# Arduino_Leonardo-REV3b_-.net
KiCad netlist of a schematic drawn in EAGLE
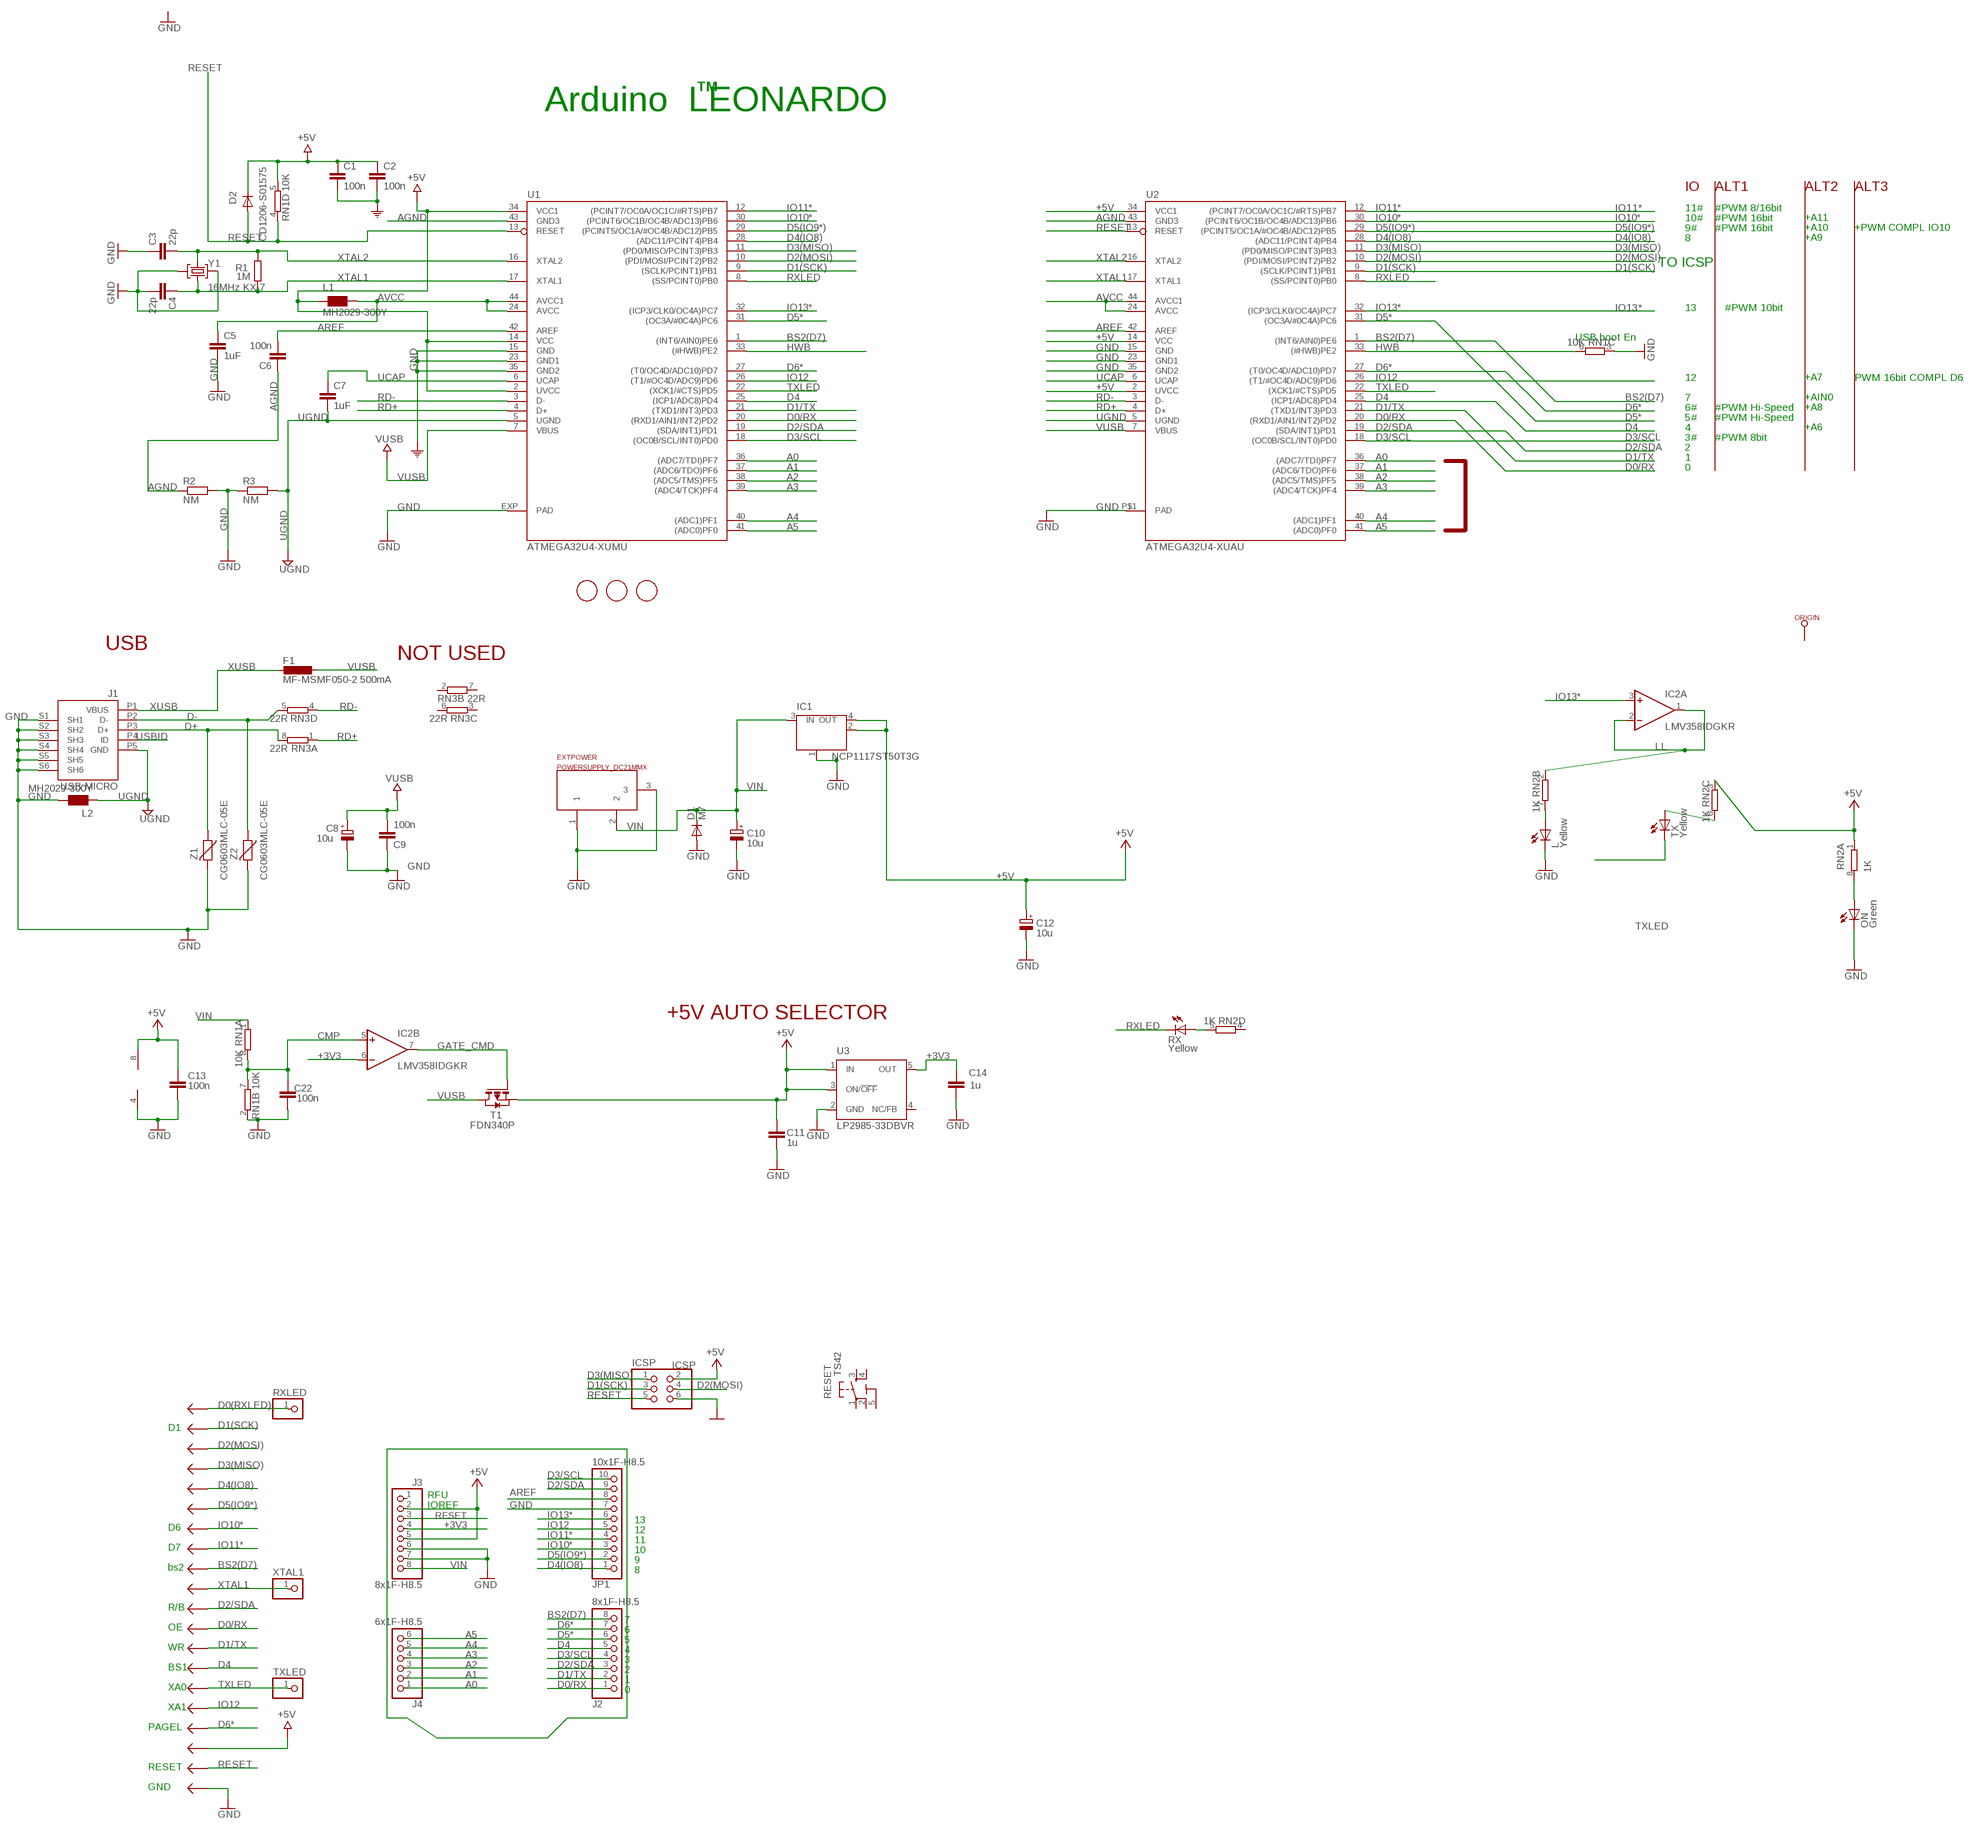
[diagram p0: schematic, sheet 1]

(export (version "E")
  (design (tool "Eeschema 10.0.6"))
  (components
    (comp (ref "C1")
      (value "100n")
      (footprint "eagle-import:C0603-ROUND")
      (libsource (lib "eagle-import") (part "C-EUC0603"))
    )
    (comp (ref "C2")
      (value "100n")
      (footprint "eagle-import:C0603-ROUND")
      (libsource (lib "eagle-import") (part "C-EUC0603"))
    )
    (comp (ref "C3")
      (value "22p")
      (footprint "eagle-import:C0603-ROUND")
      (libsource (lib "eagle-import") (part "C-EUC0603"))
    )
    (comp (ref "C4")
      (value "22p")
      (footprint "eagle-import:C0603-ROUND")
      (libsource (lib "eagle-import") (part "C-EUC0603"))
    )
    (comp (ref "C5")
      (value "1uF")
      (footprint "eagle-import:C0603-ROUND")
      (libsource (lib "eagle-import") (part "C-EUC0603"))
    )
    (comp (ref "C6")
      (value "100n")
      (footprint "eagle-import:C0603-ROUND")
      (libsource (lib "eagle-import") (part "C-EUC0603"))
    )
    (comp (ref "C7")
      (value "1uF")
      (footprint "eagle-import:C0603-ROUND")
      (libsource (lib "eagle-import") (part "C-EUC0603"))
    )
    (comp (ref "C8")
      (value "10u")
      (footprint "eagle-import:SMC_B")
      (libsource (lib "eagle-import") (part "CPOL-EUSMCB"))
    )
    (comp (ref "C9")
      (value "100n")
      (footprint "eagle-import:C0603-ROUND")
      (libsource (lib "eagle-import") (part "C-EUC0603"))
    )
    (comp (ref "C10")
      (value "10u")
      (footprint "eagle-import:SMC_B")
      (libsource (lib "eagle-import") (part "CPOL-EUSMCB"))
    )
    (comp (ref "C11")
      (value "1u")
      (footprint "eagle-import:C0603-ROUND")
      (libsource (lib "eagle-import") (part "C-EUC0603"))
    )
    (comp (ref "C12")
      (value "10u")
      (footprint "eagle-import:SMC_B")
      (libsource (lib "eagle-import") (part "CPOL-EUSMCB"))
    )
    (comp (ref "C13")
      (value "100n")
      (footprint "eagle-import:C0603-ROUND")
      (libsource (lib "eagle-import") (part "C-EUC0603"))
    )
    (comp (ref "C14")
      (value "1u")
      (footprint "eagle-import:C0603-ROUND")
      (libsource (lib "eagle-import") (part "C-EUC0603"))
    )
    (comp (ref "C22")
      (value "100n")
      (footprint "eagle-import:C0603-ROUND")
      (libsource (lib "eagle-import") (part "C-EUC0603"))
    )
    (comp (ref "D1")
      (value "M7")
      (footprint "eagle-import:SMB")
      (libsource (lib "eagle-import") (part "DIODE-SMB"))
    )
    (comp (ref "D2")
      (value "CD1206-S01575")
      (footprint "eagle-import:MINIMELF")
      (libsource (lib "eagle-import") (part "DIODE-MINIMELF"))
    )
    (comp (ref "EXTPOWER")
      (value "POWERSUPPLY_DC21MMX")
      (footprint "eagle-import:POWERSUPPLY_DC-21MM")
      (libsource (lib "eagle-import") (part "POWERSUPPLY_DC21MMX"))
    )
    (comp (ref "F1")
      (value "MF-MSMF050-2 500mA")
      (footprint "eagle-import:L1812")
      (libsource (lib "eagle-import") (part "L-EUL1812"))
    )
    (comp (ref "FID1")
      (value "FIDUCIALMOUNT")
      (footprint "eagle-import:FIDUCIA-MOUNT")
      (libsource (lib "eagle-import") (part "FIDUCIALMOUNT"))
    )
    (comp (ref "FID2")
      (value "FIDUCIALMOUNT")
      (footprint "eagle-import:FIDUCIA-MOUNT")
      (libsource (lib "eagle-import") (part "FIDUCIALMOUNT"))
    )
    (comp (ref "FID3")
      (value "FIDUCIALMOUNT")
      (footprint "eagle-import:FIDUCIA-MOUNT")
      (libsource (lib "eagle-import") (part "FIDUCIALMOUNT"))
    )
    (comp (ref "IC1")
      (value "NCP1117ST50T3G")
      (footprint "eagle-import:SOT223")
      (libsource (lib "eagle-import") (part "MC33269ST-3.3T3"))
    )
    (comp (ref "IC2")
      (value "LMV358IDGKR")
      (footprint "eagle-import:MSOP08")
      (libsource (lib "eagle-import") (part "LMV358?MMX"))
    )
    (comp (ref "ICSP")
      (value "ICSP")
      (footprint "eagle-import:2X03")
      (libsource (lib "eagle-import") (part "PINHD-2X3"))
    )
    (comp (ref "J1")
      (value "USB MICRO")
      (footprint "eagle-import:CON2_USB_MICRO_B_AT")
      (libsource (lib "eagle-import") (part "MYCON2_USB-MINI-B"))
    )
    (comp (ref "J2")
      (value "8x1F-H8.5")
      (footprint "eagle-import:1X08")
      (libsource (lib "eagle-import") (part "PINHD-1X8"))
    )
    (comp (ref "J3")
      (value "8x1F-H8.5")
      (footprint "eagle-import:1X08")
      (libsource (lib "eagle-import") (part "PINHD-1X8"))
    )
    (comp (ref "J4")
      (value "6x1F-H8.5")
      (footprint "eagle-import:1X06")
      (libsource (lib "eagle-import") (part "PINHD-1X6"))
    )
    (comp (ref "JP1")
      (value "10x1F-H8.5")
      (footprint "eagle-import:1X10")
      (libsource (lib "eagle-import") (part "PINHD-1X10"))
    )
    (comp (ref "L")
      (value "Yellow")
      (footprint "eagle-import:CHIPLED_0805")
      (libsource (lib "eagle-import") (part "LEDCHIPLED_0805"))
    )
    (comp (ref "L1")
      (value "MH2029-300Y")
      (footprint "eagle-import:0805")
      (libsource (lib "eagle-import") (part "WE-CBF_0805"))
    )
    (comp (ref "L2")
      (value "MH2029-300Y")
      (footprint "eagle-import:0805")
      (libsource (lib "eagle-import") (part "WE-CBF_0805"))
    )
    (comp (ref "ON")
      (value "Green")
      (footprint "eagle-import:CHIPLED_0805")
      (libsource (lib "eagle-import") (part "LEDCHIPLED_0805"))
    )
    (comp (ref "ORIGIN")
      (value "TP_SP")
      (footprint "eagle-import:TP-SP")
      (libsource (lib "eagle-import") (part "TP_SP"))
    )
    (comp (ref "R1")
      (value "1M")
      (footprint "eagle-import:R0603-ROUND")
      (libsource (lib "eagle-import") (part "R-EU_R0603"))
    )
    (comp (ref "R2")
      (value "NM")
      (footprint "eagle-import:R0402")
      (libsource (lib "eagle-import") (part "R-EU_R0402"))
    )
    (comp (ref "R3")
      (value "NM")
      (footprint "eagle-import:R0402")
      (libsource (lib "eagle-import") (part "R-EU_R0402"))
    )
    (comp (ref "RESET")
      (value "TS42")
      (footprint "eagle-import:TS42")
      (libsource (lib "eagle-import") (part "TS42"))
    )
    (comp (ref "RN1")
      (value "10K")
      (footprint "eagle-import:CAY16")
      (libsource (lib "eagle-import") (part "4R-NCAY16"))
    )
    (comp (ref "RN2")
      (value "1K")
      (footprint "eagle-import:CAY16")
      (libsource (lib "eagle-import") (part "4R-NCAY16"))
    )
    (comp (ref "RN3")
      (value "22R")
      (footprint "eagle-import:CAY16")
      (libsource (lib "eagle-import") (part "4R-NCAY16"))
    )
    (comp (ref "RX")
      (value "Yellow")
      (footprint "eagle-import:CHIPLED_0805")
      (libsource (lib "eagle-import") (part "LEDCHIPLED_0805"))
    )
    (comp (ref "RXLED")
      (value "PINHD-1X1")
      (footprint "eagle-import:1X01")
      (libsource (lib "eagle-import") (part "PINHD-1X1"))
    )
    (comp (ref "T1")
      (value "FDN340P")
      (footprint "eagle-import:SOT-23")
      (libsource (lib "eagle-import") (part "PMOSSOT23"))
    )
    (comp (ref "TX")
      (value "Yellow")
      (footprint "eagle-import:CHIPLED_0805")
      (libsource (lib "eagle-import") (part "LEDCHIPLED_0805"))
    )
    (comp (ref "TXLED")
      (value "PINHD-1X1")
      (footprint "eagle-import:1X01")
      (libsource (lib "eagle-import") (part "PINHD-1X1"))
    )
    (comp (ref "U$2")
      (value "PROGRAMMER_P_AVR")
      (footprint "eagle-import:PROGRAMMER_P_AVR")
      (libsource (lib "eagle-import") (part "PROGRAMMER_P_AVR"))
    )
    (comp (ref "U1")
      (value "ATMEGA32U4-XUMU")
      (footprint "eagle-import:QFN44ML7X7")
      (libsource (lib "eagle-import") (part "ATMEGA32U4-XUMU"))
    )
    (comp (ref "U2")
      (value "ATMEGA32U4-XUAU")
      (footprint "eagle-import:TQFP44-PAD")
      (libsource (lib "eagle-import") (part "ATMEGA32U4-XUAU"))
    )
    (comp (ref "U3")
      (value "LP2985-33DBVR")
      (footprint "eagle-import:SOT23-DBV")
      (libsource (lib "eagle-import") (part "LP2985-XXDBVR33"))
    )
    (comp (ref "XTAL1")
      (value "PINHD-1X1")
      (footprint "eagle-import:1X01")
      (libsource (lib "eagle-import") (part "PINHD-1X1"))
    )
    (comp (ref "Y1")
      (value "16MHz KX-7")
      (footprint "eagle-import:CRYSTAL-3.2-2.5")
      (libsource (lib "eagle-import") (part "CRYSTAL-3.2-2.5"))
    )
    (comp (ref "Z1")
      (value "CG0603MLC-05E")
      (footprint "eagle-import:CT_CN0603")
      (libsource (lib "eagle-import") (part "VARISTORCN0603"))
    )
    (comp (ref "Z2")
      (value "CG0603MLC-05E")
      (footprint "eagle-import:CT_CN0603")
      (libsource (lib "eagle-import") (part "VARISTORCN0603"))
    )
  )
  (nets
    (net (code "1") (name "+5V") (class "Default")
      (node (ref "C1") (pin "1") (pinfunction "1_1") (pintype "passive"))
      (node (ref "C11") (pin "2") (pinfunction "2_2") (pintype "passive"))
      (node (ref "C12") (pin "+") (pinfunction "+_+") (pintype "passive"))
      (node (ref "C13") (pin "1") (pinfunction "1_1") (pintype "passive"))
      (node (ref "C2") (pin "1") (pinfunction "1_1") (pintype "passive"))
      (node (ref "D2") (pin "C") (pinfunction "C_C") (pintype "passive"))
      (node (ref "IC1") (pin "2") (pinfunction "OUT_2") (pintype "passive"))
      (node (ref "IC1") (pin "4") (pinfunction "OUT_4") (pintype "passive"))
      (node (ref "IC2") (pin "8") (pinfunction "V+_8") (pintype "power_in"))
      (node (ref "ICSP") (pin "2") (pinfunction "2_2") (pintype "passive"))
      (node (ref "J3") (pin "2") (pinfunction "2_2") (pintype "passive"))
      (node (ref "J3") (pin "5") (pinfunction "5_5") (pintype "passive"))
      (node (ref "L1") (pin "1") (pinfunction "1_1") (pintype "passive"))
      (node (ref "RN1") (pin "5") (pinfunction "2_5") (pintype "passive"))
      (node (ref "RN2") (pin "1") (pinfunction "1_1") (pintype "passive"))
      (node (ref "RN2") (pin "3") (pinfunction "1_3") (pintype "passive"))
      (node (ref "T1") (pin "2") (pinfunction "S_2") (pintype "passive"))
      (node (ref "U$2") (pin "VCC") (pinfunction "VCC_VCC") (pintype "bidirectional"))
      (node (ref "U1") (pin "14") (pinfunction "VCC_14") (pintype "power_in"))
      (node (ref "U1") (pin "2") (pinfunction "UVCC_2") (pintype "power_in"))
      (node (ref "U1") (pin "34") (pinfunction "VCC1_34") (pintype "power_in"))
      (node (ref "U2") (pin "14") (pinfunction "VCC_14") (pintype "power_in"))
      (node (ref "U2") (pin "2") (pinfunction "UVCC_2") (pintype "power_in"))
      (node (ref "U2") (pin "34") (pinfunction "VCC1_34") (pintype "power_in"))
      (node (ref "U3") (pin "1") (pinfunction "IN_1") (pintype "input"))
      (node (ref "U3") (pin "3") (pinfunction "ON/~{OFF}_3") (pintype "input"))
    )
    (net (code "2") (name "/+3V3") (class "Default")
      (node (ref "C14") (pin "2") (pinfunction "2_2") (pintype "passive"))
      (node (ref "IC2") (pin "6") (pinfunction "-IN_6") (pintype "input"))
      (node (ref "J3") (pin "4") (pinfunction "4_4") (pintype "passive"))
      (node (ref "U3") (pin "5") (pinfunction "OUT_5") (pintype "passive"))
    )
    (net (code "3") (name "/5-GND") (class "Default")
      (node (ref "RESET") (pin "5") (pinfunction "5-GND_5") (pintype "power_in"))
    )
    (net (code "4") (name "/A0") (class "Default")
      (node (ref "J4") (pin "1") (pinfunction "1_1") (pintype "passive"))
      (node (ref "U1") (pin "36") (pinfunction "(ADC7/TDI)PF7_36") (pintype "bidirectional"))
      (node (ref "U2") (pin "36") (pinfunction "(ADC7/TDI)PF7_36") (pintype "bidirectional"))
    )
    (net (code "5") (name "/A1") (class "Default")
      (node (ref "J4") (pin "2") (pinfunction "2_2") (pintype "passive"))
      (node (ref "U1") (pin "37") (pinfunction "(ADC6/TDO)PF6_37") (pintype "bidirectional"))
      (node (ref "U2") (pin "37") (pinfunction "(ADC6/TDO)PF6_37") (pintype "bidirectional"))
    )
    (net (code "6") (name "/A2") (class "Default")
      (node (ref "J4") (pin "3") (pinfunction "3_3") (pintype "passive"))
      (node (ref "U1") (pin "38") (pinfunction "(ADC5/TMS)PF5_38") (pintype "bidirectional"))
      (node (ref "U2") (pin "38") (pinfunction "(ADC5/TMS)PF5_38") (pintype "bidirectional"))
    )
    (net (code "7") (name "/A3") (class "Default")
      (node (ref "J4") (pin "4") (pinfunction "4_4") (pintype "passive"))
      (node (ref "U1") (pin "39") (pinfunction "(ADC4/TCK)PF4_39") (pintype "bidirectional"))
      (node (ref "U2") (pin "39") (pinfunction "(ADC4/TCK)PF4_39") (pintype "bidirectional"))
    )
    (net (code "8") (name "/A4") (class "Default")
      (node (ref "J4") (pin "5") (pinfunction "5_5") (pintype "passive"))
      (node (ref "U1") (pin "40") (pinfunction "(ADC1)PF1_40") (pintype "bidirectional"))
      (node (ref "U2") (pin "40") (pinfunction "(ADC1)PF1_40") (pintype "bidirectional"))
    )
    (net (code "9") (name "/A5") (class "Default")
      (node (ref "J4") (pin "6") (pinfunction "6_6") (pintype "passive"))
      (node (ref "U1") (pin "41") (pinfunction "(ADC0)PF0_41") (pintype "bidirectional"))
      (node (ref "U2") (pin "41") (pinfunction "(ADC0)PF0_41") (pintype "bidirectional"))
    )
    (net (code "10") (name "/AGND") (class "Default")
      (node (ref "C6") (pin "1") (pinfunction "1_1") (pintype "passive"))
      (node (ref "R2") (pin "1") (pinfunction "1_1") (pintype "passive"))
      (node (ref "U1") (pin "43") (pinfunction "GND3_43") (pintype "power_in"))
      (node (ref "U2") (pin "43") (pinfunction "GND3_43") (pintype "power_in"))
    )
    (net (code "11") (name "/AREF") (class "Default")
      (node (ref "C6") (pin "2") (pinfunction "2_2") (pintype "passive"))
      (node (ref "JP1") (pin "8") (pinfunction "8_8") (pintype "passive"))
      (node (ref "U1") (pin "42") (pinfunction "AREF_42") (pintype "power_in"))
      (node (ref "U2") (pin "42") (pinfunction "AREF_42") (pintype "power_in"))
    )
    (net (code "12") (name "/AVCC") (class "Default")
      (node (ref "C5") (pin "1") (pinfunction "1_1") (pintype "passive"))
      (node (ref "L1") (pin "2") (pinfunction "2_2") (pintype "passive"))
      (node (ref "U1") (pin "24") (pinfunction "AVCC_24") (pintype "power_in"))
      (node (ref "U1") (pin "44") (pinfunction "AVCC1_44") (pintype "power_in"))
      (node (ref "U2") (pin "24") (pinfunction "AVCC_24") (pintype "power_in"))
      (node (ref "U2") (pin "44") (pinfunction "AVCC1_44") (pintype "power_in"))
    )
    (net (code "13") (name "/BS2(D7)") (class "Default")
      (node (ref "J2") (pin "8") (pinfunction "8_8") (pintype "passive"))
      (node (ref "U$2") (pin "BS2") (pinfunction "BS2_BS2") (pintype "bidirectional"))
      (node (ref "U1") (pin "1") (pinfunction "(INT6/AIN0)PE6_1") (pintype "bidirectional"))
      (node (ref "U2") (pin "1") (pinfunction "(INT6/AIN0)PE6_1") (pintype "bidirectional"))
    )
    (net (code "14") (name "/CMP") (class "Default")
      (node (ref "C22") (pin "2") (pinfunction "2_2") (pintype "passive"))
      (node (ref "IC2") (pin "5") (pinfunction "+IN_5") (pintype "input"))
      (node (ref "RN1") (pin "7") (pinfunction "2_7") (pintype "passive"))
      (node (ref "RN1") (pin "8") (pinfunction "2_8") (pintype "passive"))
    )
    (net (code "15") (name "/D+") (class "Default")
      (node (ref "J1") (pin "P3") (pinfunction "D+_P3") (pintype "bidirectional"))
      (node (ref "RN3") (pin "8") (pinfunction "2_8") (pintype "passive"))
      (node (ref "Z1") (pin "1") (pinfunction "1_1") (pintype "passive"))
    )
    (net (code "16") (name "/D-") (class "Default")
      (node (ref "J1") (pin "P2") (pinfunction "D-_P2") (pintype "bidirectional"))
      (node (ref "RN3") (pin "5") (pinfunction "2_5") (pintype "passive"))
      (node (ref "Z2") (pin "1") (pinfunction "1_1") (pintype "passive"))
    )
    (net (code "17") (name "/D0(RXLED)") (class "Default")
      (node (ref "RXLED") (pin "1") (pinfunction "1_1") (pintype "passive"))
      (node (ref "U$2") (pin "D0") (pinfunction "D0_D0") (pintype "bidirectional"))
    )
    (net (code "18") (name "/D0{slash}RX") (class "Default")
      (node (ref "J2") (pin "1") (pinfunction "1_1") (pintype "passive"))
      (node (ref "U$2") (pin "OE") (pinfunction "OE_OE") (pintype "bidirectional"))
      (node (ref "U1") (pin "20") (pinfunction "(RXD1/AIN1/INT2)PD2_20") (pintype "bidirectional"))
      (node (ref "U2") (pin "20") (pinfunction "(RXD1/AIN1/INT2)PD2_20") (pintype "bidirectional"))
    )
    (net (code "19") (name "/D1(SCK)") (class "Default")
      (node (ref "ICSP") (pin "3") (pinfunction "3_3") (pintype "passive"))
      (node (ref "U$2") (pin "D1") (pinfunction "D1_D1") (pintype "bidirectional"))
      (node (ref "U1") (pin "9") (pinfunction "(SCLK/PCINT1)PB1_9") (pintype "bidirectional"))
      (node (ref "U2") (pin "9") (pinfunction "(SCLK/PCINT1)PB1_9") (pintype "bidirectional"))
    )
    (net (code "20") (name "/D1{slash}TX") (class "Default")
      (node (ref "J2") (pin "2") (pinfunction "2_2") (pintype "passive"))
      (node (ref "U$2") (pin "WR") (pinfunction "WR_WR") (pintype "bidirectional"))
      (node (ref "U1") (pin "21") (pinfunction "(TXD1/INT3)PD3_21") (pintype "bidirectional"))
      (node (ref "U2") (pin "21") (pinfunction "(TXD1/INT3)PD3_21") (pintype "bidirectional"))
    )
    (net (code "21") (name "/D2(MOSI)") (class "Default")
      (node (ref "ICSP") (pin "4") (pinfunction "4_4") (pintype "passive"))
      (node (ref "U$2") (pin "D2") (pinfunction "D2_D2") (pintype "bidirectional"))
      (node (ref "U1") (pin "10") (pinfunction "(PDI/MOSI/PCINT2)PB2_10") (pintype "bidirectional"))
      (node (ref "U2") (pin "10") (pinfunction "(PDI/MOSI/PCINT2)PB2_10") (pintype "bidirectional"))
    )
    (net (code "22") (name "/D2{slash}SDA") (class "Default")
      (node (ref "J2") (pin "3") (pinfunction "3_3") (pintype "passive"))
      (node (ref "JP1") (pin "9") (pinfunction "9_9") (pintype "passive"))
      (node (ref "U$2") (pin "RB") (pinfunction "RB_RB") (pintype "bidirectional"))
      (node (ref "U1") (pin "19") (pinfunction "(SDA/INT1)PD1_19") (pintype "bidirectional"))
      (node (ref "U2") (pin "19") (pinfunction "(SDA/INT1)PD1_19") (pintype "bidirectional"))
    )
    (net (code "23") (name "/D3(MISO)") (class "Default")
      (node (ref "ICSP") (pin "1") (pinfunction "1_1") (pintype "passive"))
      (node (ref "U$2") (pin "D3") (pinfunction "D3_D3") (pintype "bidirectional"))
      (node (ref "U1") (pin "11") (pinfunction "(PD0/MISO/PCINT3)PB3_11") (pintype "bidirectional"))
      (node (ref "U2") (pin "11") (pinfunction "(PD0/MISO/PCINT3)PB3_11") (pintype "bidirectional"))
    )
    (net (code "24") (name "/D3{slash}SCL") (class "Default")
      (node (ref "J2") (pin "4") (pinfunction "4_4") (pintype "passive"))
      (node (ref "JP1") (pin "10") (pinfunction "10_10") (pintype "passive"))
      (node (ref "U1") (pin "18") (pinfunction "(OC0B/SCL/INT0)PD0_18") (pintype "bidirectional"))
      (node (ref "U2") (pin "18") (pinfunction "(OC0B/SCL/INT0)PD0_18") (pintype "bidirectional"))
    )
    (net (code "25") (name "/D4") (class "Default")
      (node (ref "J2") (pin "5") (pinfunction "5_5") (pintype "passive"))
      (node (ref "U$2") (pin "BS1") (pinfunction "BS1_BS1") (pintype "bidirectional"))
      (node (ref "U1") (pin "25") (pinfunction "(ICP1/ADC8)PD4_25") (pintype "bidirectional"))
      (node (ref "U2") (pin "25") (pinfunction "(ICP1/ADC8)PD4_25") (pintype "bidirectional"))
    )
    (net (code "26") (name "/D4(IO8)") (class "Default")
      (node (ref "JP1") (pin "1") (pinfunction "1_1") (pintype "passive"))
      (node (ref "U$2") (pin "D4") (pinfunction "D4_D4") (pintype "bidirectional"))
      (node (ref "U1") (pin "28") (pinfunction "(ADC11/PCINT4)PB4_28") (pintype "bidirectional"))
      (node (ref "U2") (pin "28") (pinfunction "(ADC11/PCINT4)PB4_28") (pintype "bidirectional"))
    )
    (net (code "27") (name "/D5(IO9*)") (class "Default")
      (node (ref "JP1") (pin "2") (pinfunction "2_2") (pintype "passive"))
      (node (ref "U$2") (pin "D5") (pinfunction "D5_D5") (pintype "bidirectional"))
      (node (ref "U1") (pin "29") (pinfunction "(PCINT5/OC1A/#OC4B/ADC12)PB5_29") (pintype "bidirectional"))
      (node (ref "U2") (pin "29") (pinfunction "(PCINT5/OC1A/#OC4B/ADC12)PB5_29") (pintype "bidirectional"))
    )
    (net (code "28") (name "/D5*") (class "Default")
      (node (ref "J2") (pin "6") (pinfunction "6_6") (pintype "passive"))
      (node (ref "U1") (pin "31") (pinfunction "(OC3A/#0C4A)PC6_31") (pintype "bidirectional"))
      (node (ref "U2") (pin "31") (pinfunction "(OC3A/#0C4A)PC6_31") (pintype "bidirectional"))
    )
    (net (code "29") (name "/D6*") (class "Default")
      (node (ref "J2") (pin "7") (pinfunction "7_7") (pintype "passive"))
      (node (ref "U$2") (pin "PAGEL") (pinfunction "PAGEL_PAGEL") (pintype "bidirectional"))
      (node (ref "U1") (pin "27") (pinfunction "(T0/OC4D/ADC10)PD7_27") (pintype "bidirectional"))
      (node (ref "U2") (pin "27") (pinfunction "(T0/OC4D/ADC10)PD7_27") (pintype "bidirectional"))
    )
    (net (code "30") (name "/GATE_CMD") (class "Default")
      (node (ref "IC2") (pin "7") (pinfunction "OUT_7") (pintype "output"))
      (node (ref "T1") (pin "3") (pinfunction "G_3") (pintype "passive"))
    )
    (net (code "31") (name "/HWB") (class "Default")
      (node (ref "RN1") (pin "6") (pinfunction "2_6") (pintype "passive"))
      (node (ref "U1") (pin "33") (pinfunction "(#HWB)PE2_33") (pintype "bidirectional"))
      (node (ref "U2") (pin "33") (pinfunction "(#HWB)PE2_33") (pintype "bidirectional"))
    )
    (net (code "32") (name "/IO10*") (class "Default")
      (node (ref "JP1") (pin "3") (pinfunction "3_3") (pintype "passive"))
      (node (ref "U$2") (pin "D6") (pinfunction "D6_D6") (pintype "bidirectional"))
      (node (ref "U1") (pin "30") (pinfunction "(PCINT6/OC1B/OC4B/ADC13)PB6_30") (pintype "bidirectional"))
      (node (ref "U2") (pin "30") (pinfunction "(PCINT6/OC1B/OC4B/ADC13)PB6_30") (pintype "bidirectional"))
    )
    (net (code "33") (name "/IO11*") (class "Default")
      (node (ref "JP1") (pin "4") (pinfunction "4_4") (pintype "passive"))
      (node (ref "U$2") (pin "D7") (pinfunction "D7_D7") (pintype "bidirectional"))
      (node (ref "U1") (pin "12") (pinfunction "(PCINT7/OC0A/OC1C/#RTS)PB7_12") (pintype "bidirectional"))
      (node (ref "U2") (pin "12") (pinfunction "(PCINT7/OC0A/OC1C/#RTS)PB7_12") (pintype "bidirectional"))
    )
    (net (code "34") (name "/IO12") (class "Default")
      (node (ref "JP1") (pin "5") (pinfunction "5_5") (pintype "passive"))
      (node (ref "U$2") (pin "XA1") (pinfunction "XA1_XA1") (pintype "bidirectional"))
      (node (ref "U1") (pin "26") (pinfunction "(T1/#OC4D/ADC9)PD6_26") (pintype "bidirectional"))
      (node (ref "U2") (pin "26") (pinfunction "(T1/#OC4D/ADC9)PD6_26") (pintype "bidirectional"))
    )
    (net (code "35") (name "/IO13*") (class "Default")
      (node (ref "IC2") (pin "3") (pinfunction "+IN_3") (pintype "input"))
      (node (ref "JP1") (pin "6") (pinfunction "6_6") (pintype "passive"))
      (node (ref "U1") (pin "32") (pinfunction "(ICP3/CLK0/OC4A)PC7_32") (pintype "bidirectional"))
      (node (ref "U2") (pin "32") (pinfunction "(ICP3/CLK0/OC4A)PC7_32") (pintype "bidirectional"))
    )
    (net (code "36") (name "/LL") (class "Default")
      (node (ref "IC2") (pin "1") (pinfunction "OUT_1") (pintype "output"))
      (node (ref "IC2") (pin "2") (pinfunction "-IN_2") (pintype "input"))
      (node (ref "RN2") (pin "2") (pinfunction "1_2") (pintype "passive"))
    )
    (net (code "37") (name "/RD+") (class "Default")
      (node (ref "RN3") (pin "1") (pinfunction "1_1") (pintype "passive"))
      (node (ref "U1") (pin "4") (pinfunction "D+_4") (pintype "bidirectional"))
      (node (ref "U2") (pin "4") (pinfunction "D+_4") (pintype "bidirectional"))
    )
    (net (code "38") (name "/RD-") (class "Default")
      (node (ref "RN3") (pin "4") (pinfunction "1_4") (pintype "passive"))
      (node (ref "U1") (pin "3") (pinfunction "D-_3") (pintype "bidirectional"))
      (node (ref "U2") (pin "3") (pinfunction "D-_3") (pintype "bidirectional"))
    )
    (net (code "39") (name "/RESET") (class "Default")
      (node (ref "D2") (pin "A") (pinfunction "A_A") (pintype "passive"))
      (node (ref "ICSP") (pin "5") (pinfunction "5_5") (pintype "passive"))
      (node (ref "J3") (pin "3") (pinfunction "3_3") (pintype "passive"))
      (node (ref "RN1") (pin "4") (pinfunction "1_4") (pintype "passive"))
      (node (ref "U$2") (pin "RESET") (pinfunction "RESET_RESET") (pintype "bidirectional"))
      (node (ref "U1") (pin "13") (pinfunction "RESET_13") (pintype "input"))
      (node (ref "U2") (pin "13") (pinfunction "RESET_13") (pintype "input"))
    )
    (net (code "40") (name "/RXLED") (class "Default")
      (node (ref "RX") (pin "C") (pinfunction "C_C") (pintype "passive"))
      (node (ref "U1") (pin "8") (pinfunction "(SS/PCINT0)PB0_8") (pintype "bidirectional"))
      (node (ref "U2") (pin "8") (pinfunction "(SS/PCINT0)PB0_8") (pintype "bidirectional"))
    )
    (net (code "41") (name "/TXLED") (class "Default")
      (node (ref "TX") (pin "C") (pinfunction "C_C") (pintype "passive"))
      (node (ref "TXLED") (pin "1") (pinfunction "1_1") (pintype "passive"))
      (node (ref "U$2") (pin "XA0") (pinfunction "XA0_XA0") (pintype "bidirectional"))
      (node (ref "U1") (pin "22") (pinfunction "(XCK1/#CTS)PD5_22") (pintype "bidirectional"))
      (node (ref "U2") (pin "22") (pinfunction "(XCK1/#CTS)PD5_22") (pintype "bidirectional"))
    )
    (net (code "42") (name "/UCAP") (class "Default")
      (node (ref "C7") (pin "1") (pinfunction "1_1") (pintype "passive"))
      (node (ref "U1") (pin "6") (pinfunction "UCAP_6") (pintype "passive"))
      (node (ref "U2") (pin "6") (pinfunction "UCAP_6") (pintype "passive"))
    )
    (net (code "43") (name "/USBID") (class "Default")
      (node (ref "J1") (pin "P4") (pinfunction "ID_P4") (pintype "bidirectional"))
    )
    (net (code "44") (name "/VIN") (class "Default")
      (node (ref "C10") (pin "+") (pinfunction "+_+") (pintype "passive"))
      (node (ref "D1") (pin "C") (pinfunction "C_C") (pintype "passive"))
      (node (ref "EXTPOWER") (pin "2") (pinfunction "2_2") (pintype "power_in"))
      (node (ref "IC1") (pin "3") (pinfunction "IN_3") (pintype "input"))
      (node (ref "J3") (pin "8") (pinfunction "8_8") (pintype "passive"))
      (node (ref "RN1") (pin "1") (pinfunction "1_1") (pintype "passive"))
    )
    (net (code "45") (name "/XTAL1") (class "Default")
      (node (ref "C4") (pin "1") (pinfunction "1_1") (pintype "passive"))
      (node (ref "R1") (pin "1") (pinfunction "1_1") (pintype "passive"))
      (node (ref "U$2") (pin "XTAL1") (pinfunction "XTAL1_XTAL1") (pintype "bidirectional"))
      (node (ref "U1") (pin "17") (pinfunction "XTAL1_17") (pintype "bidirectional"))
      (node (ref "U2") (pin "17") (pinfunction "XTAL1_17") (pintype "bidirectional"))
      (node (ref "XTAL1") (pin "1") (pinfunction "1_1") (pintype "passive"))
      (node (ref "Y1") (pin "1") (pinfunction "C1_1") (pintype "passive"))
    )
    (net (code "46") (name "/XTAL2") (class "Default")
      (node (ref "C3") (pin "2") (pinfunction "2_2") (pintype "passive"))
      (node (ref "R1") (pin "2") (pinfunction "2_2") (pintype "passive"))
      (node (ref "U1") (pin "16") (pinfunction "XTAL2_16") (pintype "bidirectional"))
      (node (ref "U2") (pin "16") (pinfunction "XTAL2_16") (pintype "bidirectional"))
      (node (ref "Y1") (pin "3") (pinfunction "C2_3") (pintype "passive"))
    )
    (net (code "47") (name "/XUSB") (class "Default")
      (node (ref "F1") (pin "2") (pinfunction "2_2") (pintype "passive"))
      (node (ref "J1") (pin "P1") (pinfunction "VBUS_P1") (pintype "power_in"))
    )
    (net (code "48") (name "COM") (class "Default")
      (node (ref "C1") (pin "2") (pinfunction "2_2") (pintype "passive"))
      (node (ref "C10") (pin "-") (pinfunction "-_-") (pintype "passive"))
      (node (ref "C11") (pin "1") (pinfunction "1_1") (pintype "passive"))
      (node (ref "C12") (pin "-") (pinfunction "-_-") (pintype "passive"))
      (node (ref "C13") (pin "2") (pinfunction "2_2") (pintype "passive"))
      (node (ref "C14") (pin "1") (pinfunction "1_1") (pintype "passive"))
      (node (ref "C2") (pin "2") (pinfunction "2_2") (pintype "passive"))
      (node (ref "C22") (pin "1") (pinfunction "1_1") (pintype "passive"))
      (node (ref "C3") (pin "1") (pinfunction "1_1") (pintype "passive"))
      (node (ref "C4") (pin "2") (pinfunction "2_2") (pintype "passive"))
      (node (ref "C5") (pin "2") (pinfunction "2_2") (pintype "passive"))
      (node (ref "C8") (pin "-") (pinfunction "-_-") (pintype "passive"))
      (node (ref "C9") (pin "1") (pinfunction "1_1") (pintype "passive"))
      (node (ref "D1") (pin "A") (pinfunction "A_A") (pintype "passive"))
      (node (ref "EXTPOWER") (pin "1") (pinfunction "1_1") (pintype "power_in"))
      (node (ref "EXTPOWER") (pin "3") (pinfunction "3_3") (pintype "power_in"))
      (node (ref "IC1") (pin "1") (pinfunction "GND/ADJ_1") (pintype "input"))
      (node (ref "IC2") (pin "4") (pinfunction "V-_4") (pintype "power_in"))
      (node (ref "ICSP") (pin "6") (pinfunction "6_6") (pintype "passive"))
      (node (ref "J1") (pin "S1") (pinfunction "SH1_S1") (pintype "passive"))
      (node (ref "J1") (pin "S2") (pinfunction "SH2_S2") (pintype "passive"))
      (node (ref "J1") (pin "S3") (pinfunction "SH3_S3") (pintype "passive"))
      (node (ref "J1") (pin "S4") (pinfunction "SH4_S4") (pintype "passive"))
      (node (ref "J1") (pin "S5") (pinfunction "SH5_S5") (pintype "passive"))
      (node (ref "J1") (pin "S6") (pinfunction "SH6_S6") (pintype "passive"))
      (node (ref "J3") (pin "6") (pinfunction "6_6") (pintype "passive"))
      (node (ref "J3") (pin "7") (pinfunction "7_7") (pintype "passive"))
      (node (ref "JP1") (pin "7") (pinfunction "7_7") (pintype "passive"))
      (node (ref "L") (pin "C") (pinfunction "C_C") (pintype "passive"))
      (node (ref "L2") (pin "2") (pinfunction "2_2") (pintype "passive"))
      (node (ref "ON") (pin "C") (pinfunction "C_C") (pintype "passive"))
      (node (ref "R2") (pin "2") (pinfunction "2_2") (pintype "passive"))
      (node (ref "R3") (pin "1") (pinfunction "1_1") (pintype "passive"))
      (node (ref "RN1") (pin "2") (pinfunction "1_2") (pintype "passive"))
      (node (ref "RN1") (pin "3") (pinfunction "1_3") (pintype "passive"))
      (node (ref "U$2") (pin "GND") (pinfunction "GND_GND") (pintype "bidirectional"))
      (node (ref "U$2") (pin "GND01") (pinfunction "GND_GND01") (pintype "bidirectional"))
      (node (ref "U$2") (pin "GND03") (pinfunction "GND_GND03") (pintype "bidirectional"))
      (node (ref "U$2") (pin "GND04") (pinfunction "GND_GND04") (pintype "bidirectional"))
      (node (ref "U$2") (pin "GND05") (pinfunction "GND_GND05") (pintype "bidirectional"))
      (node (ref "U$2") (pin "GND06") (pinfunction "GND_GND06") (pintype "bidirectional"))
      (node (ref "U$2") (pin "GND07") (pinfunction "GND_GND07") (pintype "bidirectional"))
      (node (ref "U$2") (pin "GND08") (pinfunction "GND_GND08") (pintype "bidirectional"))
      (node (ref "U$2") (pin "GND09") (pinfunction "GND_GND09") (pintype "bidirectional"))
      (node (ref "U$2") (pin "GND10") (pinfunction "GND_GND10") (pintype "bidirectional"))
      (node (ref "U$2") (pin "GND11") (pinfunction "GND_GND11") (pintype "bidirectional"))
      (node (ref "U$2") (pin "GND12") (pinfunction "GND_GND12") (pintype "bidirectional"))
      (node (ref "U$2") (pin "GND13") (pinfunction "GND_GND13") (pintype "bidirectional"))
      (node (ref "U$2") (pin "GND14") (pinfunction "GND_GND14") (pintype "bidirectional"))
      (node (ref "U$2") (pin "GND15") (pinfunction "GND_GND15") (pintype "bidirectional"))
      (node (ref "U$2") (pin "GND16") (pinfunction "GND_GND16") (pintype "bidirectional"))
      (node (ref "U$2") (pin "GND17") (pinfunction "GND_GND17") (pintype "bidirectional"))
      (node (ref "U$2") (pin "GND18") (pinfunction "GND_GND18") (pintype "bidirectional"))
      (node (ref "U$2") (pin "GND19") (pinfunction "GND_GND19") (pintype "bidirectional"))
      (node (ref "U$2") (pin "GND2") (pinfunction "GND_GND2") (pintype "bidirectional"))
      (node (ref "U$2") (pin "GND20") (pinfunction "GND_GND20") (pintype "bidirectional"))
      (node (ref "U$2") (pin "GND21") (pinfunction "GND_GND21") (pintype "bidirectional"))
      (node (ref "U$2") (pin "GND22") (pinfunction "GND_GND22") (pintype "bidirectional"))
      (node (ref "U1") (pin "15") (pinfunction "GND_15") (pintype "power_in"))
      (node (ref "U1") (pin "23") (pinfunction "GND1_23") (pintype "power_in"))
      (node (ref "U1") (pin "35") (pinfunction "GND2_35") (pintype "power_in"))
      (node (ref "U1") (pin "EXP") (pinfunction "PAD_EXP") (pintype "power_in"))
      (node (ref "U2") (pin "15") (pinfunction "GND_15") (pintype "power_in"))
      (node (ref "U2") (pin "23") (pinfunction "GND1_23") (pintype "power_in"))
      (node (ref "U2") (pin "35") (pinfunction "GND2_35") (pintype "power_in"))
      (node (ref "U2") (pin "P$1") (pinfunction "PAD_P$1") (pintype "power_in"))
      (node (ref "U3") (pin "2") (pinfunction "GND_2") (pintype "power_in"))
      (node (ref "Y1") (pin "2") (pinfunction "GND_2") (pintype "passive"))
      (node (ref "Y1") (pin "4") (pinfunction "GND_4") (pintype "passive"))
      (node (ref "Z1") (pin "2") (pinfunction "2_2") (pintype "passive"))
      (node (ref "Z2") (pin "2") (pinfunction "2_2") (pintype "passive"))
    )
    (net (code "49") (name "Net-(RN2A-2)") (class "Default")
      (node (ref "ON") (pin "A") (pinfunction "A_A") (pintype "passive"))
      (node (ref "RN2") (pin "8") (pinfunction "2_8") (pintype "passive"))
    )
    (net (code "50") (name "Net-(RN2B-2)") (class "Default")
      (node (ref "L") (pin "A") (pinfunction "A_A") (pintype "passive"))
      (node (ref "RN2") (pin "7") (pinfunction "2_7") (pintype "passive"))
    )
    (net (code "51") (name "Net-(RN2C-2)") (class "Default")
      (node (ref "RN2") (pin "6") (pinfunction "2_6") (pintype "passive"))
      (node (ref "TX") (pin "A") (pinfunction "A_A") (pintype "passive"))
    )
    (net (code "52") (name "Net-(RN2D-2)") (class "Default")
      (node (ref "RN2") (pin "5") (pinfunction "2_5") (pintype "passive"))
      (node (ref "RX") (pin "A") (pinfunction "A_A") (pintype "passive"))
    )
    (net (code "53") (name "UGND") (class "Default")
      (node (ref "C7") (pin "2") (pinfunction "2_2") (pintype "passive"))
      (node (ref "J1") (pin "P5") (pinfunction "GND_P5") (pintype "passive"))
      (node (ref "L2") (pin "1") (pinfunction "1_1") (pintype "passive"))
      (node (ref "R3") (pin "2") (pinfunction "2_2") (pintype "passive"))
      (node (ref "U1") (pin "5") (pinfunction "UGND_5") (pintype "power_in"))
      (node (ref "U2") (pin "5") (pinfunction "UGND_5") (pintype "power_in"))
    )
    (net (code "54") (name "VUSB") (class "Default")
      (node (ref "C8") (pin "+") (pinfunction "+_+") (pintype "passive"))
      (node (ref "C9") (pin "2") (pinfunction "2_2") (pintype "passive"))
      (node (ref "F1") (pin "1") (pinfunction "1_1") (pintype "passive"))
      (node (ref "T1") (pin "1") (pinfunction "D_1") (pintype "passive"))
      (node (ref "U1") (pin "7") (pinfunction "VBUS_7") (pintype "input"))
      (node (ref "U2") (pin "7") (pinfunction "VBUS_7") (pintype "input"))
    )
    (net (code "55") (name "unconnected-(J3-Pad1)") (class "Default")
      (node (ref "J3") (pin "1") (pinfunction "1_1") (pintype "passive"))
    )
    (net (code "56") (name "unconnected-(ORIGIN-TESTP-PadX)") (class "Default")
      (node (ref "ORIGIN") (pin "X") (pinfunction "TESTP_X") (pintype "passive"))
    )
    (net (code "57") (name "unconnected-(RESET-Pad1)") (class "Default")
      (node (ref "RESET") (pin "1") (pinfunction "1_1") (pintype "passive"))
    )
    (net (code "58") (name "unconnected-(RESET-Pad2)") (class "Default")
      (node (ref "RESET") (pin "2") (pinfunction "2_2") (pintype "passive"))
    )
    (net (code "59") (name "unconnected-(RESET-Pad3)") (class "Default")
      (node (ref "RESET") (pin "3") (pinfunction "3_3") (pintype "passive"))
    )
    (net (code "60") (name "unconnected-(RESET-Pad4)") (class "Default")
      (node (ref "RESET") (pin "4") (pinfunction "4_4") (pintype "passive"))
    )
    (net (code "61") (name "unconnected-(RN2D-1-Pad4)") (class "Default")
      (node (ref "RN2") (pin "4") (pinfunction "1_4") (pintype "passive"))
    )
    (net (code "62") (name "unconnected-(RN3B-1-Pad2)") (class "Default")
      (node (ref "RN3") (pin "2") (pinfunction "1_2") (pintype "passive"))
    )
    (net (code "63") (name "unconnected-(RN3B-2-Pad7)") (class "Default")
      (node (ref "RN3") (pin "7") (pinfunction "2_7") (pintype "passive"))
    )
    (net (code "64") (name "unconnected-(RN3C-1-Pad3)") (class "Default")
      (node (ref "RN3") (pin "3") (pinfunction "1_3") (pintype "passive"))
    )
    (net (code "65") (name "unconnected-(RN3C-2-Pad6)") (class "Default")
      (node (ref "RN3") (pin "6") (pinfunction "2_6") (pintype "passive"))
    )
    (net (code "66") (name "unconnected-(U3-NC{slash}FB-Pad4)") (class "Default")
      (node (ref "U3") (pin "4") (pinfunction "NC/FB_4") (pintype "passive"))
    )
  )
)
